# Constant_Current.net
KiCad netlist of a schematic drawn in EAGLE
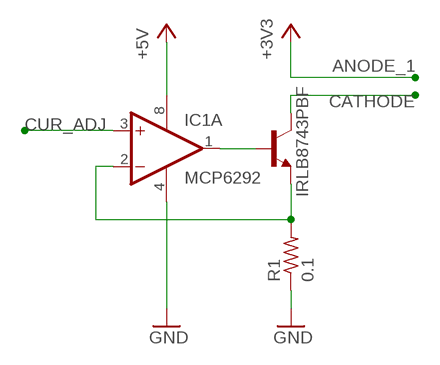
[diagram p0: schematic, sheet 1]
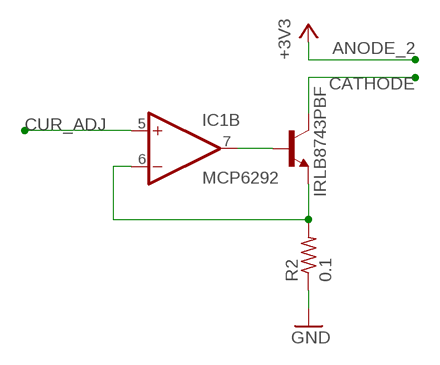
[diagram p1: schematic, sheet 2]
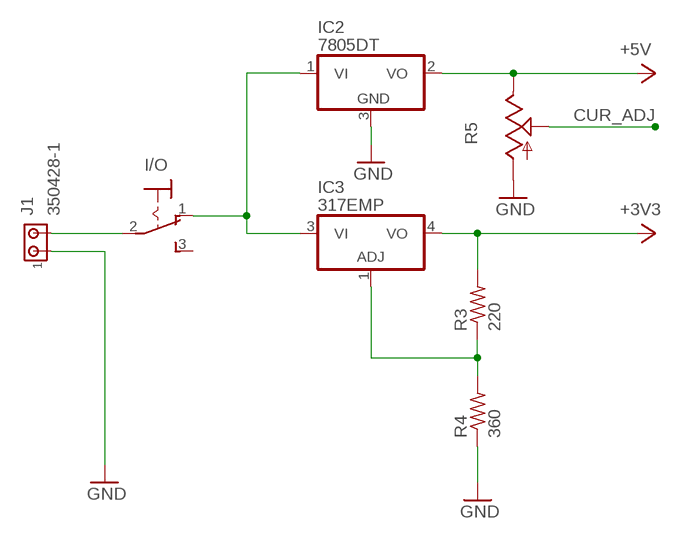
[diagram p2: schematic, sheet 3]
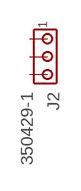
[diagram p3: schematic, sheet 5]

(export (version "E")
  (design (tool "Eeschema 10.0.6"))
  (components
    (comp (ref "IC1")
      (value "MCP6292")
      (footprint "eagle-import:SO08")
      (libsource (lib "eagle-import") (part "2AMP_P8+4D"))
    )
    (comp (ref "R1")
      (value "0.1")
      (footprint "eagle-import:R1206")
      (libsource (lib "eagle-import") (part "R-US_R1206"))
    )
    (comp (ref "T1")
      (value "IRLB8743PBF")
      (footprint "eagle-import:TO220BV")
      (libsource (lib "eagle-import") (part "2SC1306"))
    )
    (comp (ref "J2")
      (value "350429-1")
      (footprint "eagle-import:350429-1")
      (libsource (lib "eagle-import") (part "350429-1"))
    )
    (comp (ref "I/O")
      (value "M9040P")
      (footprint "eagle-import:M9040P")
      (libsource (lib "eagle-import") (part "M9040P"))
    )
    (comp (ref "IC2")
      (value "7805DT")
      (footprint "eagle-import:TO252")
      (libsource (lib "eagle-import") (part "78DT05"))
    )
    (comp (ref "IC3")
      (value "317EMP")
      (footprint "eagle-import:SOT223")
      (libsource (lib "eagle-import") (part "317EMP"))
    )
    (comp (ref "J1")
      (value "350428-1")
      (footprint "eagle-import:350428-1")
      (libsource (lib "eagle-import") (part "350428-1"))
    )
    (comp (ref "R3")
      (value "220")
      (footprint "eagle-import:M1206")
      (libsource (lib "eagle-import") (part "R-US_M1206"))
    )
    (comp (ref "R4")
      (value "360")
      (footprint "eagle-import:M1206")
      (libsource (lib "eagle-import") (part "R-US_M1206"))
    )
    (comp (ref "R5")
      (value "TRIM_US-RJ9W")
      (footprint "eagle-import:RJ9W")
      (libsource (lib "eagle-import") (part "TRIM_US-RJ9W"))
    )
    (comp (ref "R2")
      (value "0.1")
      (footprint "eagle-import:R1206")
      (libsource (lib "eagle-import") (part "R-US_R1206"))
    )
    (comp (ref "T2")
      (value "IRLB8743PBF")
      (footprint "eagle-import:TO220BV")
      (libsource (lib "eagle-import") (part "2SC1306"))
    )
  )
  (nets
    (net (code "1") (name "+5V") (class "Default")
      (node (ref "IC1") (pin "8") (pinfunction "V+_8") (pintype "power_in"))
      (node (ref "IC2") (pin "2") (pinfunction "VO_2") (pintype "passive"))
      (node (ref "R5") (pin "E") (pinfunction "E_E") (pintype "passive"))
    )
    (net (code "2") (name "ANODE_1") (class "Default")
      (node (ref "IC3") (pin "4") (pinfunction "VO_4") (pintype "passive"))
      (node (ref "R3") (pin "2") (pinfunction "2_2") (pintype "passive"))
    )
    (net (code "3") (name "CATHODE") (class "Default")
      (node (ref "T1") (pin "2") (pinfunction "C_2") (pintype "passive"))
      (node (ref "T2") (pin "2") (pinfunction "C_2") (pintype "passive"))
    )
    (net (code "4") (name "CUR_ADJ") (class "Default")
      (node (ref "IC1") (pin "3") (pinfunction "+IN_3") (pintype "input"))
      (node (ref "IC1") (pin "5") (pinfunction "+IN_5") (pintype "input"))
      (node (ref "R5") (pin "S") (pinfunction "S_S") (pintype "passive"))
    )
    (net (code "5") (name "GND") (class "Default")
      (node (ref "IC1") (pin "4") (pinfunction "V-_4") (pintype "power_in"))
      (node (ref "IC2") (pin "3") (pinfunction "GND_3") (pintype "passive"))
      (node (ref "J1") (pin "1") (pinfunction "1_1") (pintype "passive"))
      (node (ref "R1") (pin "1") (pinfunction "1_1") (pintype "passive"))
      (node (ref "R2") (pin "1") (pinfunction "1_1") (pintype "passive"))
      (node (ref "R4") (pin "1") (pinfunction "1_1") (pintype "passive"))
      (node (ref "R5") (pin "A") (pinfunction "A_A") (pintype "passive"))
    )
    (net (code "6") (name "Net-(I/O-O)") (class "Default")
      (node (ref "I/O") (pin "1") (pinfunction "O_1") (pintype "passive"))
      (node (ref "IC2") (pin "1") (pinfunction "VI_1") (pintype "input"))
      (node (ref "IC3") (pin "3") (pinfunction "VI_3") (pintype "input"))
    )
    (net (code "7") (name "Net-(I/O-P)") (class "Default")
      (node (ref "I/O") (pin "2") (pinfunction "P_2") (pintype "passive"))
      (node (ref "J1") (pin "2") (pinfunction "2_2") (pintype "passive"))
    )
    (net (code "8") (name "Net-(IC1A--IN)") (class "Default")
      (node (ref "IC1") (pin "2") (pinfunction "-IN_2") (pintype "input"))
      (node (ref "R1") (pin "2") (pinfunction "2_2") (pintype "passive"))
      (node (ref "T1") (pin "3") (pinfunction "E_3") (pintype "passive"))
    )
    (net (code "9") (name "Net-(IC1A-OUT)") (class "Default")
      (node (ref "IC1") (pin "1") (pinfunction "OUT_1") (pintype "output"))
      (node (ref "T1") (pin "1") (pinfunction "B_1") (pintype "passive"))
    )
    (net (code "10") (name "Net-(IC1B--IN)") (class "Default")
      (node (ref "IC1") (pin "6") (pinfunction "-IN_6") (pintype "input"))
      (node (ref "R2") (pin "2") (pinfunction "2_2") (pintype "passive"))
      (node (ref "T2") (pin "3") (pinfunction "E_3") (pintype "passive"))
    )
    (net (code "11") (name "Net-(IC1B-OUT)") (class "Default")
      (node (ref "IC1") (pin "7") (pinfunction "OUT_7") (pintype "output"))
      (node (ref "T2") (pin "1") (pinfunction "B_1") (pintype "passive"))
    )
    (net (code "12") (name "Net-(IC3-ADJ)") (class "Default")
      (node (ref "IC3") (pin "1") (pinfunction "ADJ_1") (pintype "input"))
      (node (ref "R3") (pin "1") (pinfunction "1_1") (pintype "passive"))
      (node (ref "R4") (pin "2") (pinfunction "2_2") (pintype "passive"))
    )
    (net (code "13") (name "unconnected-(I/O-S-Pad3)") (class "Default")
      (node (ref "I/O") (pin "3") (pinfunction "S_3") (pintype "passive"))
    )
    (net (code "14") (name "unconnected-(J2-Pad1)") (class "Default")
      (node (ref "J2") (pin "1") (pinfunction "1_1") (pintype "passive"))
    )
    (net (code "15") (name "unconnected-(J2-Pad2)") (class "Default")
      (node (ref "J2") (pin "2") (pinfunction "2_2") (pintype "passive"))
    )
    (net (code "16") (name "unconnected-(J2-Pad3)") (class "Default")
      (node (ref "J2") (pin "3") (pinfunction "3_3") (pintype "passive"))
    )
  )
)
